# EMS_esp32_wifi_lora_gsm_v2_7.net
KiCad netlist of a schematic drawn in EAGLE
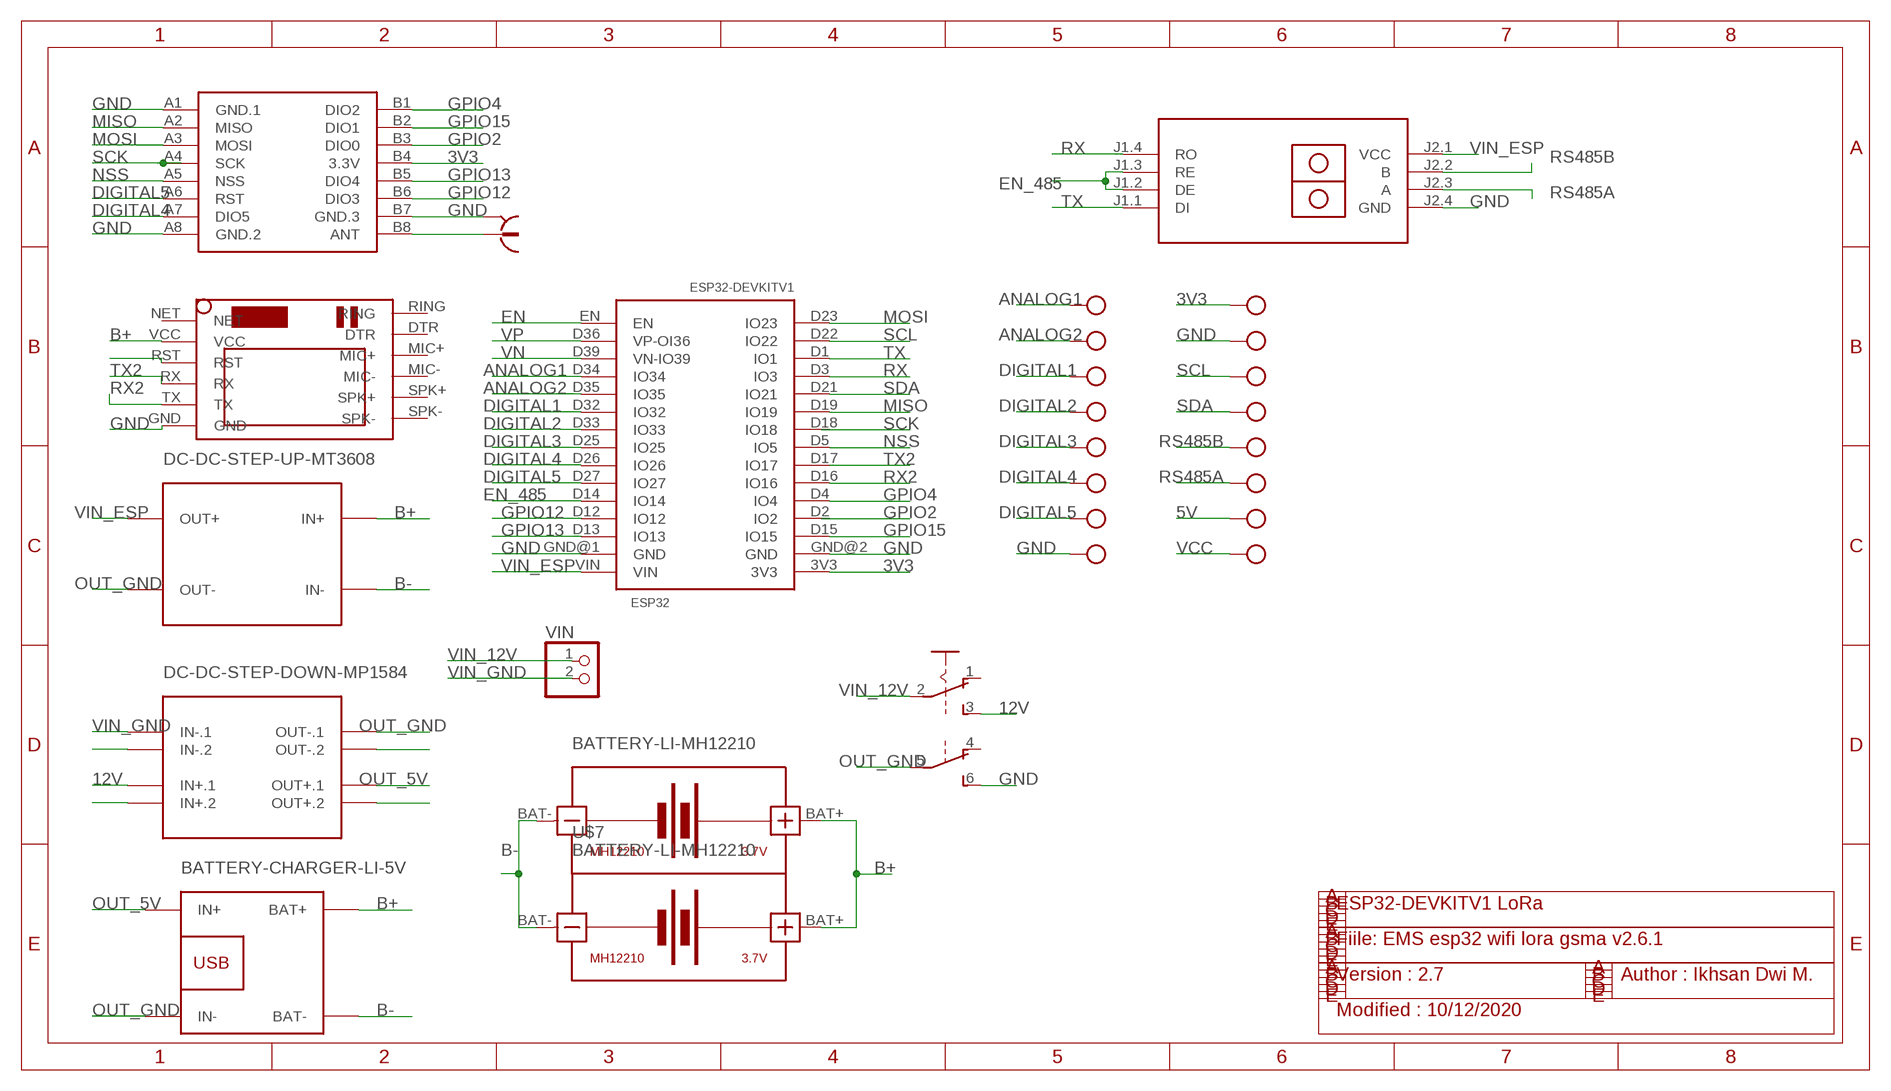
[diagram p0: schematic, sheet 1]

(export (version "E")
  (design (tool "Eeschema 10.0.6"))
  (components
    (comp (ref "ESP32")
      (value "ESP32DEVKITV1")
      (footprint "eagle-import:ESP32-DEVKITV1")
      (libsource (lib "eagle-import") (part "ESP32DEVKITV1"))
    )
    (comp (ref "S1")
      (value "A68-A31")
      (footprint "eagle-import:A68-A31")
      (libsource (lib "eagle-import") (part "A68-A31"))
    )
    (comp (ref "U$1")
      (value "RS485-TTL-CONVERTER")
      (footprint "eagle-import:RS485-TTL-CONVERTER")
      (libsource (lib "eagle-import") (part "RS485-TTL-CONVERTER"))
    )
    (comp (ref "U$2")
      (value "DC-DC-STEP-UP-MT3608")
      (footprint "eagle-import:DC-DC-STEP-UP-MT3608")
      (libsource (lib "eagle-import") (part "DC-DC-STEP-UP-MT3608"))
    )
    (comp (ref "U$3")
      (value "DC-DC-STEP-DOWN-MP1584")
      (footprint "eagle-import:DC-DC-STEP-DOWN-MP1584")
      (libsource (lib "eagle-import") (part "DC-DC-STEP-DOWN-MP1584"))
    )
    (comp (ref "U$4")
      (value "BATTERY-CHARGER-LI-5V")
      (footprint "eagle-import:BATTERY-CHARGER-LI-5V")
      (libsource (lib "eagle-import") (part "BATTERY-CHARGER-LI-5V"))
    )
    (comp (ref "U$5")
      (value "WIRELESS-LORA-RFM95W#SMD")
      (footprint "eagle-import:WIRELESS-LORA-RFM95W#SMD")
      (libsource (lib "eagle-import") (part "WIRELESS-LORA-RFM95W#SMD"))
    )
    (comp (ref "U$6")
      (value "BATTERY-LI-MH12210")
      (footprint "eagle-import:BATTERY-LI-MH12210")
      (libsource (lib "eagle-import") (part "BATTERY-LI-MH12210"))
    )
    (comp (ref "U$7")
      (value "BATTERY-LI-MH12210")
      (footprint "eagle-import:BATTERY-LI-MH12210")
      (libsource (lib "eagle-import") (part "BATTERY-LI-MH12210"))
    )
    (comp (ref "U$9")
      (value "SIM800LMODULE")
      (footprint "eagle-import:SIM800LMODULE")
      (libsource (lib "eagle-import") (part "SIM800LMODULE"))
    )
    (comp (ref "VIN")
      (value "PINHD-1X2")
      (footprint "eagle-import:1X02")
      (libsource (lib "eagle-import") (part "PINHD-1X2"))
    )
    (comp (ref "X1")
      (value "734120110")
      (footprint "eagle-import:734120110")
      (libsource (lib "eagle-import") (part "734120110"))
    )
    (comp (ref "X2")
      (value "MKDSN1,5/2-5,08")
      (footprint "eagle-import:MKDSN1,5_2-5,08")
      (libsource (lib "eagle-import") (part "MKDSN1,5/2-5,08"))
    )
    (comp (ref "X3")
      (value "MKDSN1,5/2-5,08")
      (footprint "eagle-import:MKDSN1,5_2-5,08")
      (libsource (lib "eagle-import") (part "MKDSN1,5/2-5,08"))
    )
    (comp (ref "X4")
      (value "MKDSN1,5/2-5,08")
      (footprint "eagle-import:MKDSN1,5_2-5,08")
      (libsource (lib "eagle-import") (part "MKDSN1,5/2-5,08"))
    )
    (comp (ref "X5")
      (value "MKDSN1,5/2-5,08")
      (footprint "eagle-import:MKDSN1,5_2-5,08")
      (libsource (lib "eagle-import") (part "MKDSN1,5/2-5,08"))
    )
    (comp (ref "X6")
      (value "MKDSN1,5/2-5,08")
      (footprint "eagle-import:MKDSN1,5_2-5,08")
      (libsource (lib "eagle-import") (part "MKDSN1,5/2-5,08"))
    )
    (comp (ref "X7")
      (value "MKDSN1,5/2-5,08")
      (footprint "eagle-import:MKDSN1,5_2-5,08")
      (libsource (lib "eagle-import") (part "MKDSN1,5/2-5,08"))
    )
    (comp (ref "X8")
      (value "MKDSN1,5/2-5,08")
      (footprint "eagle-import:MKDSN1,5_2-5,08")
      (libsource (lib "eagle-import") (part "MKDSN1,5/2-5,08"))
    )
    (comp (ref "X9")
      (value "MKDSN1,5/2-5,08")
      (footprint "eagle-import:MKDSN1,5_2-5,08")
      (libsource (lib "eagle-import") (part "MKDSN1,5/2-5,08"))
    )
  )
  (nets
    (net (code "1") (name "/3V3") (class "Default")
      (node (ref "ESP32") (pin "3V3") (pinfunction "3V3_3V3") (pintype "bidirectional"))
      (node (ref "U$5") (pin "B4") (pinfunction "3.3V_B4") (pintype "power_in"))
      (node (ref "X4") (pin "1") (pinfunction "KL_1") (pintype "passive"))
    )
    (net (code "2") (name "/5V") (class "Default")
      (node (ref "X9") (pin "1") (pinfunction "KL_1") (pintype "passive"))
    )
    (net (code "3") (name "/12V") (class "Default")
      (node (ref "S1") (pin "3") (pinfunction "S_3") (pintype "passive"))
      (node (ref "U$3") (pin "IN+.1") (pinfunction "IN+.1_IN+.1") (pintype "bidirectional"))
    )
    (net (code "4") (name "/ANALOG1") (class "Default")
      (node (ref "ESP32") (pin "D34") (pinfunction "IO34_D34") (pintype "bidirectional"))
      (node (ref "X2") (pin "1") (pinfunction "KL_1") (pintype "passive"))
    )
    (net (code "5") (name "/ANALOG2") (class "Default")
      (node (ref "ESP32") (pin "D35") (pinfunction "IO35_D35") (pintype "bidirectional"))
      (node (ref "X2") (pin "2") (pinfunction "KL_2") (pintype "passive"))
    )
    (net (code "6") (name "/B+") (class "Default")
      (node (ref "U$2") (pin "IN+") (pinfunction "IN+_IN+") (pintype "bidirectional"))
      (node (ref "U$4") (pin "BAT+") (pinfunction "BAT+_BAT+") (pintype "bidirectional"))
      (node (ref "U$6") (pin "BAT+") (pinfunction "BAT+_BAT+") (pintype "power_in"))
      (node (ref "U$7") (pin "BAT+") (pinfunction "BAT+_BAT+") (pintype "power_in"))
      (node (ref "U$9") (pin "VCC") (pinfunction "VCC_VCC") (pintype "bidirectional"))
    )
    (net (code "7") (name "/B-") (class "Default")
      (node (ref "U$2") (pin "IN-") (pinfunction "IN-_IN-") (pintype "bidirectional"))
      (node (ref "U$4") (pin "BAT-") (pinfunction "BAT-_BAT-") (pintype "bidirectional"))
      (node (ref "U$6") (pin "BAT-") (pinfunction "BAT-_BAT-") (pintype "power_in"))
      (node (ref "U$7") (pin "BAT-") (pinfunction "BAT-_BAT-") (pintype "power_in"))
    )
    (net (code "8") (name "/DIGITAL1") (class "Default")
      (node (ref "ESP32") (pin "D32") (pinfunction "IO32_D32") (pintype "bidirectional"))
      (node (ref "X3") (pin "1") (pinfunction "KL_1") (pintype "passive"))
    )
    (net (code "9") (name "/DIGITAL2") (class "Default")
      (node (ref "ESP32") (pin "D33") (pinfunction "IO33_D33") (pintype "bidirectional"))
      (node (ref "X3") (pin "2") (pinfunction "KL_2") (pintype "passive"))
    )
    (net (code "10") (name "/DIGITAL3") (class "Default")
      (node (ref "ESP32") (pin "D25") (pinfunction "IO25_D25") (pintype "bidirectional"))
      (node (ref "X5") (pin "1") (pinfunction "KL_1") (pintype "passive"))
    )
    (net (code "11") (name "/DIGITAL4") (class "Default")
      (node (ref "ESP32") (pin "D26") (pinfunction "IO26_D26") (pintype "bidirectional"))
      (node (ref "U$5") (pin "A7") (pinfunction "DIO5_A7") (pintype "bidirectional"))
      (node (ref "X5") (pin "2") (pinfunction "KL_2") (pintype "passive"))
    )
    (net (code "12") (name "/DIGITAL5") (class "Default")
      (node (ref "ESP32") (pin "D27") (pinfunction "IO27_D27") (pintype "bidirectional"))
      (node (ref "U$5") (pin "A6") (pinfunction "RST_A6") (pintype "bidirectional"))
      (node (ref "X6") (pin "1") (pinfunction "KL_1") (pintype "passive"))
    )
    (net (code "13") (name "/EN") (class "Default")
      (node (ref "ESP32") (pin "EN") (pinfunction "EN_EN") (pintype "bidirectional"))
    )
    (net (code "14") (name "/EN_485") (class "Default")
      (node (ref "ESP32") (pin "D14") (pinfunction "IO14_D14") (pintype "bidirectional"))
      (node (ref "U$1") (pin "J1.2") (pinfunction "DE_J1.2") (pintype "passive"))
      (node (ref "U$1") (pin "J1.3") (pinfunction "RE_J1.3") (pintype "passive"))
    )
    (net (code "15") (name "/GND") (class "Default")
      (node (ref "ESP32") (pin "GND@1") (pinfunction "GND_GND@1") (pintype "bidirectional"))
      (node (ref "ESP32") (pin "GND@2") (pinfunction "GND_GND@2") (pintype "bidirectional"))
      (node (ref "S1") (pin "6") (pinfunction "S_6") (pintype "passive"))
      (node (ref "U$1") (pin "J2.4") (pinfunction "GND_J2.4") (pintype "power_in"))
      (node (ref "U$5") (pin "A1") (pinfunction "GND.1_A1") (pintype "power_in"))
      (node (ref "U$5") (pin "A8") (pinfunction "GND.2_A8") (pintype "power_in"))
      (node (ref "U$5") (pin "B7") (pinfunction "GND.3_B7") (pintype "power_in"))
      (node (ref "U$9") (pin "GND") (pinfunction "GND_GND") (pintype "bidirectional"))
      (node (ref "X1") (pin "S@1") (pinfunction "2_S@1") (pintype "passive"))
      (node (ref "X1") (pin "S@2") (pinfunction "2_S@2") (pintype "passive"))
      (node (ref "X1") (pin "S@3") (pinfunction "2_S@3") (pintype "passive"))
      (node (ref "X4") (pin "2") (pinfunction "KL_2") (pintype "passive"))
      (node (ref "X6") (pin "2") (pinfunction "KL_2") (pintype "passive"))
    )
    (net (code "16") (name "/GPIO2") (class "Default")
      (node (ref "ESP32") (pin "D2") (pinfunction "IO2_D2") (pintype "bidirectional"))
      (node (ref "U$5") (pin "B3") (pinfunction "DIO0_B3") (pintype "bidirectional"))
    )
    (net (code "17") (name "/GPIO4") (class "Default")
      (node (ref "ESP32") (pin "D4") (pinfunction "IO4_D4") (pintype "bidirectional"))
      (node (ref "U$5") (pin "B1") (pinfunction "DIO2_B1") (pintype "bidirectional"))
    )
    (net (code "18") (name "/GPIO12") (class "Default")
      (node (ref "ESP32") (pin "D12") (pinfunction "IO12_D12") (pintype "bidirectional"))
      (node (ref "U$5") (pin "B6") (pinfunction "DIO3_B6") (pintype "bidirectional"))
    )
    (net (code "19") (name "/GPIO13") (class "Default")
      (node (ref "ESP32") (pin "D13") (pinfunction "IO13_D13") (pintype "bidirectional"))
      (node (ref "U$5") (pin "B5") (pinfunction "DIO4_B5") (pintype "bidirectional"))
    )
    (net (code "20") (name "/GPIO15") (class "Default")
      (node (ref "ESP32") (pin "D15") (pinfunction "IO15_D15") (pintype "bidirectional"))
      (node (ref "U$5") (pin "B2") (pinfunction "DIO1_B2") (pintype "bidirectional"))
    )
    (net (code "21") (name "/MISO") (class "Default")
      (node (ref "ESP32") (pin "D19") (pinfunction "IO19_D19") (pintype "bidirectional"))
      (node (ref "U$5") (pin "A2") (pinfunction "MISO_A2") (pintype "bidirectional"))
    )
    (net (code "22") (name "/MOSI") (class "Default")
      (node (ref "ESP32") (pin "D23") (pinfunction "IO23_D23") (pintype "bidirectional"))
      (node (ref "U$5") (pin "A3") (pinfunction "MOSI_A3") (pintype "bidirectional"))
    )
    (net (code "23") (name "/NSS") (class "Default")
      (node (ref "ESP32") (pin "D5") (pinfunction "IO5_D5") (pintype "bidirectional"))
      (node (ref "U$5") (pin "A5") (pinfunction "NSS_A5") (pintype "bidirectional"))
    )
    (net (code "24") (name "/OUT_5V") (class "Default")
      (node (ref "U$3") (pin "OUT+.1") (pinfunction "OUT+.1_OUT+.1") (pintype "bidirectional"))
      (node (ref "U$4") (pin "IN+") (pinfunction "IN+_IN+") (pintype "bidirectional"))
    )
    (net (code "25") (name "/OUT_GND") (class "Default")
      (node (ref "S1") (pin "5") (pinfunction "P_5") (pintype "passive"))
      (node (ref "U$2") (pin "OUT-") (pinfunction "OUT-_OUT-") (pintype "bidirectional"))
      (node (ref "U$3") (pin "OUT-.1") (pinfunction "OUT-.1_OUT-.1") (pintype "bidirectional"))
      (node (ref "U$4") (pin "IN-") (pinfunction "IN-_IN-") (pintype "bidirectional"))
    )
    (net (code "26") (name "/RS485A") (class "Default")
      (node (ref "U$1") (pin "J2.3") (pinfunction "A_J2.3") (pintype "passive"))
      (node (ref "X8") (pin "2") (pinfunction "KL_2") (pintype "passive"))
    )
    (net (code "27") (name "/RS485B") (class "Default")
      (node (ref "U$1") (pin "J2.2") (pinfunction "B_J2.2") (pintype "passive"))
      (node (ref "X8") (pin "1") (pinfunction "KL_1") (pintype "passive"))
    )
    (net (code "28") (name "/RX") (class "Default")
      (node (ref "ESP32") (pin "D3") (pinfunction "IO3_D3") (pintype "bidirectional"))
      (node (ref "U$1") (pin "J1.4") (pinfunction "RO_J1.4") (pintype "passive"))
    )
    (net (code "29") (name "/RX2") (class "Default")
      (node (ref "ESP32") (pin "D16") (pinfunction "IO16_D16") (pintype "bidirectional"))
      (node (ref "U$9") (pin "TX") (pinfunction "TX_TX") (pintype "bidirectional"))
    )
    (net (code "30") (name "/SCK") (class "Default")
      (node (ref "ESP32") (pin "D18") (pinfunction "IO18_D18") (pintype "bidirectional"))
      (node (ref "U$5") (pin "A4") (pinfunction "SCK_A4") (pintype "bidirectional"))
    )
    (net (code "31") (name "/SCL") (class "Default")
      (node (ref "ESP32") (pin "D22") (pinfunction "IO22_D22") (pintype "bidirectional"))
      (node (ref "X7") (pin "1") (pinfunction "KL_1") (pintype "passive"))
    )
    (net (code "32") (name "/SDA") (class "Default")
      (node (ref "ESP32") (pin "D21") (pinfunction "IO21_D21") (pintype "bidirectional"))
      (node (ref "X7") (pin "2") (pinfunction "KL_2") (pintype "passive"))
    )
    (net (code "33") (name "/TX") (class "Default")
      (node (ref "ESP32") (pin "D1") (pinfunction "IO1_D1") (pintype "bidirectional"))
      (node (ref "U$1") (pin "J1.1") (pinfunction "DI_J1.1") (pintype "passive"))
    )
    (net (code "34") (name "/TX2") (class "Default")
      (node (ref "ESP32") (pin "D17") (pinfunction "IO17_D17") (pintype "bidirectional"))
      (node (ref "U$9") (pin "RX") (pinfunction "RX_RX") (pintype "bidirectional"))
    )
    (net (code "35") (name "/VCC") (class "Default")
      (node (ref "X9") (pin "2") (pinfunction "KL_2") (pintype "passive"))
    )
    (net (code "36") (name "/VIN_12V") (class "Default")
      (node (ref "S1") (pin "2") (pinfunction "P_2") (pintype "passive"))
      (node (ref "VIN") (pin "1") (pinfunction "1_1") (pintype "passive"))
    )
    (net (code "37") (name "/VIN_ESP") (class "Default")
      (node (ref "ESP32") (pin "VIN") (pinfunction "VIN_VIN") (pintype "bidirectional"))
      (node (ref "U$1") (pin "J2.1") (pinfunction "VCC_J2.1") (pintype "power_in"))
      (node (ref "U$2") (pin "OUT+") (pinfunction "OUT+_OUT+") (pintype "bidirectional"))
    )
    (net (code "38") (name "/VIN_GND") (class "Default")
      (node (ref "U$3") (pin "IN-.1") (pinfunction "IN-.1_IN-.1") (pintype "bidirectional"))
      (node (ref "VIN") (pin "2") (pinfunction "2_2") (pintype "passive"))
    )
    (net (code "39") (name "/VN") (class "Default")
      (node (ref "ESP32") (pin "D39") (pinfunction "VN-IO39_D39") (pintype "bidirectional"))
    )
    (net (code "40") (name "/VP") (class "Default")
      (node (ref "ESP32") (pin "D36") (pinfunction "VP-OI36_D36") (pintype "bidirectional"))
    )
    (net (code "41") (name "Net-(U$5-ANT)") (class "Default")
      (node (ref "U$5") (pin "B8") (pinfunction "ANT_B8") (pintype "passive"))
      (node (ref "X1") (pin "1") (pinfunction "1_1") (pintype "passive"))
    )
    (net (code "42") (name "unconnected-(S1A-O-Pad1)") (class "Default")
      (node (ref "S1") (pin "1") (pinfunction "O_1") (pintype "passive"))
    )
    (net (code "43") (name "unconnected-(S1B-O-Pad4)") (class "Default")
      (node (ref "S1") (pin "4") (pinfunction "O_4") (pintype "passive"))
    )
    (net (code "44") (name "unconnected-(U$3-PadIN+.2)") (class "Default")
      (node (ref "U$3") (pin "IN+.2") (pinfunction "IN+.2_IN+.2") (pintype "bidirectional"))
    )
    (net (code "45") (name "unconnected-(U$3-PadIN-.2)") (class "Default")
      (node (ref "U$3") (pin "IN-.2") (pinfunction "IN-.2_IN-.2") (pintype "bidirectional"))
    )
    (net (code "46") (name "unconnected-(U$3-PadOUT+.2)") (class "Default")
      (node (ref "U$3") (pin "OUT+.2") (pinfunction "OUT+.2_OUT+.2") (pintype "bidirectional"))
    )
    (net (code "47") (name "unconnected-(U$3-PadOUT-.2)") (class "Default")
      (node (ref "U$3") (pin "OUT-.2") (pinfunction "OUT-.2_OUT-.2") (pintype "bidirectional"))
    )
    (net (code "48") (name "unconnected-(U$9-PadDTR)") (class "Default")
      (node (ref "U$9") (pin "DTR") (pinfunction "DTR_DTR") (pintype "bidirectional"))
    )
    (net (code "49") (name "unconnected-(U$9-PadMIC+)") (class "Default")
      (node (ref "U$9") (pin "MIC+") (pinfunction "MIC+_MIC+") (pintype "bidirectional"))
    )
    (net (code "50") (name "unconnected-(U$9-PadMIC-)") (class "Default")
      (node (ref "U$9") (pin "MIC-") (pinfunction "MIC-_MIC-") (pintype "bidirectional"))
    )
    (net (code "51") (name "unconnected-(U$9-PadNET)") (class "Default")
      (node (ref "U$9") (pin "NET") (pinfunction "NET_NET") (pintype "bidirectional"))
    )
    (net (code "52") (name "unconnected-(U$9-PadRING)") (class "Default")
      (node (ref "U$9") (pin "RING") (pinfunction "RING_RING") (pintype "bidirectional"))
    )
    (net (code "53") (name "unconnected-(U$9-PadRST)") (class "Default")
      (node (ref "U$9") (pin "RST") (pinfunction "RST_RST") (pintype "bidirectional"))
    )
    (net (code "54") (name "unconnected-(U$9-PadSPK+)") (class "Default")
      (node (ref "U$9") (pin "SPK+") (pinfunction "SPK+_SPK+") (pintype "bidirectional"))
    )
    (net (code "55") (name "unconnected-(U$9-PadSPK-)") (class "Default")
      (node (ref "U$9") (pin "SPK-") (pinfunction "SPK-_SPK-") (pintype "bidirectional"))
    )
  )
)
